# ArduinoShield.net
KiCad netlist of a schematic drawn in EAGLE
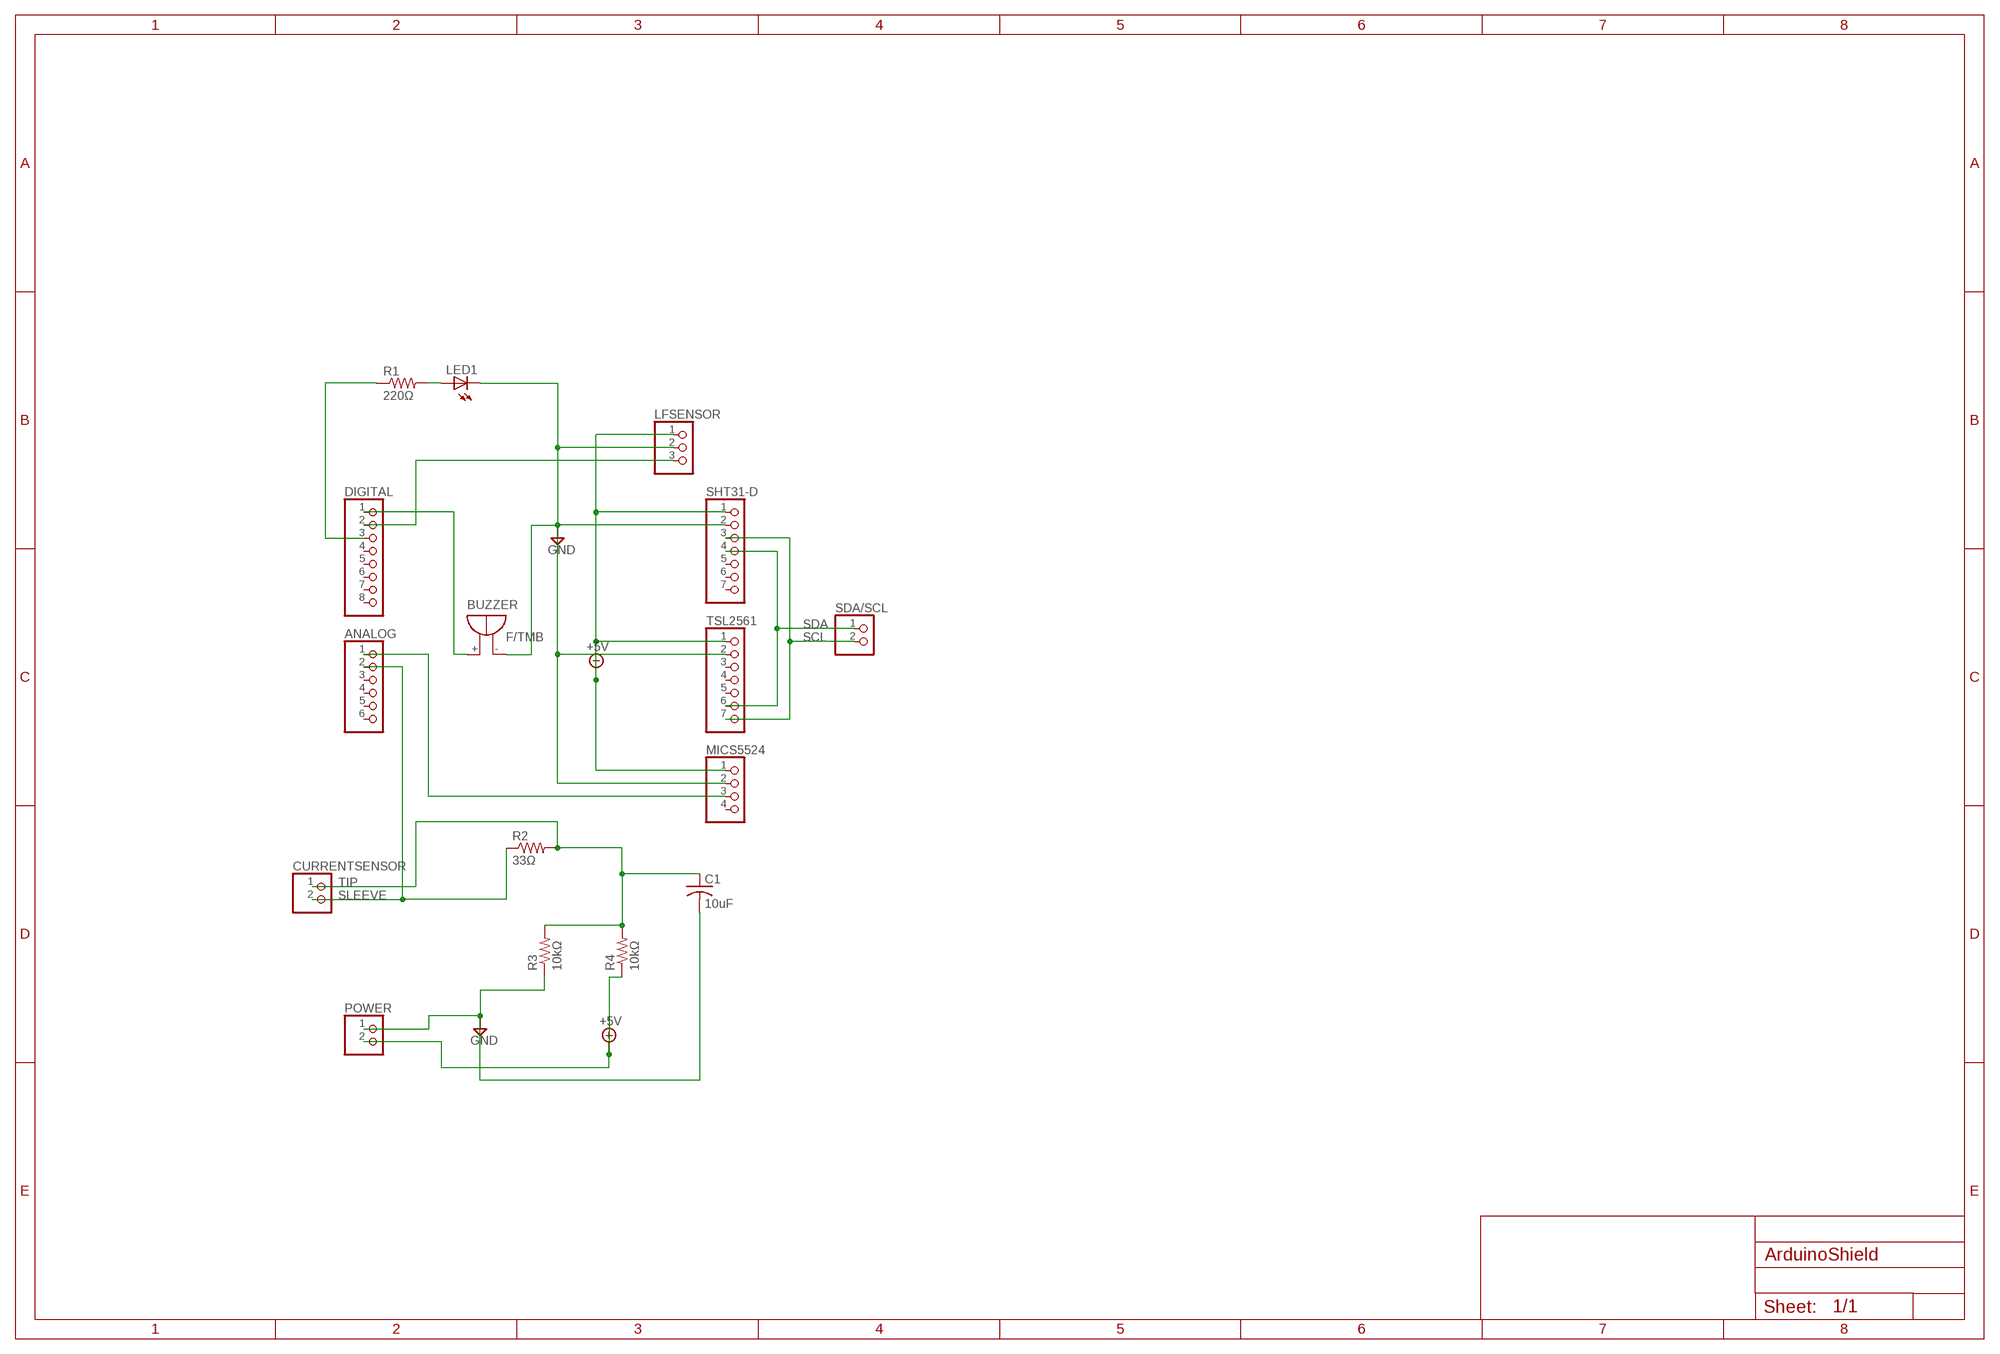
[diagram p0: schematic, sheet 1]

(export (version "E")
  (design (tool "Eeschema 10.0.6"))
  (components
    (comp (ref "ANALOG")
      (value "PINHD-1X6")
      (footprint "eagle-import:1X06")
      (libsource (lib "eagle-import") (part "PINHD-1X6"))
    )
    (comp (ref "BUZZER")
      (value "F/TMB")
      (footprint "eagle-import:F_TMB")
      (libsource (lib "eagle-import") (part "F/TMB"))
    )
    (comp (ref "C1")
      (value "10uF")
      (footprint "eagle-import:C025-060X050")
      (libsource (lib "eagle-import") (part "C-US025-060X050"))
    )
    (comp (ref "CURRENTSENSOR")
      (value "PINHD-1X2")
      (footprint "eagle-import:1X02")
      (libsource (lib "eagle-import") (part "PINHD-1X2"))
    )
    (comp (ref "DIGITAL")
      (value "PINHD-1X8")
      (footprint "eagle-import:1X08")
      (libsource (lib "eagle-import") (part "PINHD-1X8"))
    )
    (comp (ref "LED1")
      (value "LED5MM")
      (footprint "eagle-import:LED5MM")
      (libsource (lib "eagle-import") (part "LED5MM"))
    )
    (comp (ref "LFSENSOR")
      (value "PINHD-1X3")
      (footprint "eagle-import:1X03")
      (libsource (lib "eagle-import") (part "PINHD-1X3"))
    )
    (comp (ref "MICS5524")
      (value "PINHD-1X4")
      (footprint "eagle-import:1X04")
      (libsource (lib "eagle-import") (part "PINHD-1X4"))
    )
    (comp (ref "POWER")
      (value "PINHD-1X2")
      (footprint "eagle-import:1X02")
      (libsource (lib "eagle-import") (part "PINHD-1X2"))
    )
    (comp (ref "R1")
      (value "220Ω")
      (footprint "eagle-import:0309_12")
      (libsource (lib "eagle-import") (part "R-US_0309/12"))
    )
    (comp (ref "R2")
      (value "33Ω")
      (footprint "eagle-import:0309_12")
      (libsource (lib "eagle-import") (part "R-US_0309/12"))
    )
    (comp (ref "R3")
      (value "10kΩ")
      (footprint "eagle-import:0309_12")
      (libsource (lib "eagle-import") (part "R-US_0309/12"))
    )
    (comp (ref "R4")
      (value "10kΩ")
      (footprint "eagle-import:0309_12")
      (libsource (lib "eagle-import") (part "R-US_0309/12"))
    )
    (comp (ref "SDA/SCL")
      (value "PINHD-1X2")
      (footprint "eagle-import:1X02")
      (libsource (lib "eagle-import") (part "PINHD-1X2"))
    )
    (comp (ref "SHT31-D")
      (value "PINHD-1X7")
      (footprint "eagle-import:1X07")
      (libsource (lib "eagle-import") (part "PINHD-1X7"))
    )
    (comp (ref "TSL2561")
      (value "PINHD-1X7")
      (footprint "eagle-import:1X07")
      (libsource (lib "eagle-import") (part "PINHD-1X7"))
    )
  )
  (nets
    (net (code "1") (name "+5V") (class "Default")
      (node (ref "LFSENSOR") (pin "1") (pinfunction "1_1") (pintype "passive"))
      (node (ref "MICS5524") (pin "1") (pinfunction "1_1") (pintype "passive"))
      (node (ref "POWER") (pin "2") (pinfunction "2_2") (pintype "passive"))
      (node (ref "R4") (pin "1") (pinfunction "1_1") (pintype "passive"))
      (node (ref "SHT31-D") (pin "1") (pinfunction "1_1") (pintype "passive"))
      (node (ref "TSL2561") (pin "1") (pinfunction "1_1") (pintype "passive"))
    )
    (net (code "2") (name "/SCL") (class "Default")
      (node (ref "SDA/SCL") (pin "2") (pinfunction "2_2") (pintype "passive"))
      (node (ref "SHT31-D") (pin "3") (pinfunction "3_3") (pintype "passive"))
      (node (ref "TSL2561") (pin "7") (pinfunction "7_7") (pintype "passive"))
    )
    (net (code "3") (name "/SDA") (class "Default")
      (node (ref "SDA/SCL") (pin "1") (pinfunction "1_1") (pintype "passive"))
      (node (ref "SHT31-D") (pin "4") (pinfunction "4_4") (pintype "passive"))
      (node (ref "TSL2561") (pin "6") (pinfunction "6_6") (pintype "passive"))
    )
    (net (code "4") (name "/SLEEVE") (class "Default")
      (node (ref "ANALOG") (pin "2") (pinfunction "2_2") (pintype "passive"))
      (node (ref "CURRENTSENSOR") (pin "2") (pinfunction "2_2") (pintype "passive"))
      (node (ref "R2") (pin "1") (pinfunction "1_1") (pintype "passive"))
    )
    (net (code "5") (name "/TIP") (class "Default")
      (node (ref "C1") (pin "1") (pinfunction "1_1") (pintype "passive"))
      (node (ref "CURRENTSENSOR") (pin "1") (pinfunction "1_1") (pintype "passive"))
      (node (ref "R2") (pin "2") (pinfunction "2_2") (pintype "passive"))
      (node (ref "R3") (pin "2") (pinfunction "2_2") (pintype "passive"))
      (node (ref "R4") (pin "2") (pinfunction "2_2") (pintype "passive"))
    )
    (net (code "6") (name "GND") (class "Default")
      (node (ref "BUZZER") (pin "-") (pinfunction "-_-") (pintype "passive"))
      (node (ref "C1") (pin "2") (pinfunction "2_2") (pintype "passive"))
      (node (ref "LED1") (pin "K") (pinfunction "C_K") (pintype "passive"))
      (node (ref "LFSENSOR") (pin "2") (pinfunction "2_2") (pintype "passive"))
      (node (ref "MICS5524") (pin "2") (pinfunction "2_2") (pintype "passive"))
      (node (ref "POWER") (pin "1") (pinfunction "1_1") (pintype "passive"))
      (node (ref "R3") (pin "1") (pinfunction "1_1") (pintype "passive"))
      (node (ref "SHT31-D") (pin "2") (pinfunction "2_2") (pintype "passive"))
      (node (ref "TSL2561") (pin "2") (pinfunction "2_2") (pintype "passive"))
    )
    (net (code "7") (name "Net-(ANALOG-Pad1)") (class "Default")
      (node (ref "ANALOG") (pin "1") (pinfunction "1_1") (pintype "passive"))
      (node (ref "MICS5524") (pin "3") (pinfunction "3_3") (pintype "passive"))
    )
    (net (code "8") (name "Net-(BUZZER-Pad+)") (class "Default")
      (node (ref "BUZZER") (pin "+") (pinfunction "+_+") (pintype "passive"))
      (node (ref "DIGITAL") (pin "1") (pinfunction "1_1") (pintype "passive"))
    )
    (net (code "9") (name "Net-(DIGITAL-Pad2)") (class "Default")
      (node (ref "DIGITAL") (pin "2") (pinfunction "2_2") (pintype "passive"))
      (node (ref "LFSENSOR") (pin "3") (pinfunction "3_3") (pintype "passive"))
    )
    (net (code "10") (name "Net-(DIGITAL-Pad3)") (class "Default")
      (node (ref "DIGITAL") (pin "3") (pinfunction "3_3") (pintype "passive"))
      (node (ref "R1") (pin "1") (pinfunction "1_1") (pintype "passive"))
    )
    (net (code "11") (name "Net-(LED1-PadA)") (class "Default")
      (node (ref "LED1") (pin "A") (pinfunction "A_A") (pintype "passive"))
      (node (ref "R1") (pin "2") (pinfunction "2_2") (pintype "passive"))
    )
    (net (code "12") (name "unconnected-(ANALOG-Pad3)") (class "Default")
      (node (ref "ANALOG") (pin "3") (pinfunction "3_3") (pintype "passive"))
    )
    (net (code "13") (name "unconnected-(ANALOG-Pad4)") (class "Default")
      (node (ref "ANALOG") (pin "4") (pinfunction "4_4") (pintype "passive"))
    )
    (net (code "14") (name "unconnected-(ANALOG-Pad5)") (class "Default")
      (node (ref "ANALOG") (pin "5") (pinfunction "5_5") (pintype "passive"))
    )
    (net (code "15") (name "unconnected-(ANALOG-Pad6)") (class "Default")
      (node (ref "ANALOG") (pin "6") (pinfunction "6_6") (pintype "passive"))
    )
    (net (code "16") (name "unconnected-(DIGITAL-Pad4)") (class "Default")
      (node (ref "DIGITAL") (pin "4") (pinfunction "4_4") (pintype "passive"))
    )
    (net (code "17") (name "unconnected-(DIGITAL-Pad5)") (class "Default")
      (node (ref "DIGITAL") (pin "5") (pinfunction "5_5") (pintype "passive"))
    )
    (net (code "18") (name "unconnected-(DIGITAL-Pad6)") (class "Default")
      (node (ref "DIGITAL") (pin "6") (pinfunction "6_6") (pintype "passive"))
    )
    (net (code "19") (name "unconnected-(DIGITAL-Pad7)") (class "Default")
      (node (ref "DIGITAL") (pin "7") (pinfunction "7_7") (pintype "passive"))
    )
    (net (code "20") (name "unconnected-(DIGITAL-Pad8)") (class "Default")
      (node (ref "DIGITAL") (pin "8") (pinfunction "8_8") (pintype "passive"))
    )
    (net (code "21") (name "unconnected-(MICS5524-Pad4)") (class "Default")
      (node (ref "MICS5524") (pin "4") (pinfunction "4_4") (pintype "passive"))
    )
    (net (code "22") (name "unconnected-(SHT31-D-Pad5)") (class "Default")
      (node (ref "SHT31-D") (pin "5") (pinfunction "5_5") (pintype "passive"))
    )
    (net (code "23") (name "unconnected-(SHT31-D-Pad6)") (class "Default")
      (node (ref "SHT31-D") (pin "6") (pinfunction "6_6") (pintype "passive"))
    )
    (net (code "24") (name "unconnected-(SHT31-D-Pad7)") (class "Default")
      (node (ref "SHT31-D") (pin "7") (pinfunction "7_7") (pintype "passive"))
    )
    (net (code "25") (name "unconnected-(TSL2561-Pad3)") (class "Default")
      (node (ref "TSL2561") (pin "3") (pinfunction "3_3") (pintype "passive"))
    )
    (net (code "26") (name "unconnected-(TSL2561-Pad4)") (class "Default")
      (node (ref "TSL2561") (pin "4") (pinfunction "4_4") (pintype "passive"))
    )
    (net (code "27") (name "unconnected-(TSL2561-Pad5)") (class "Default")
      (node (ref "TSL2561") (pin "5") (pinfunction "5_5") (pintype "passive"))
    )
  )
)
